# MRCS-odTester.net
KiCad netlist of a schematic drawn in EAGLE
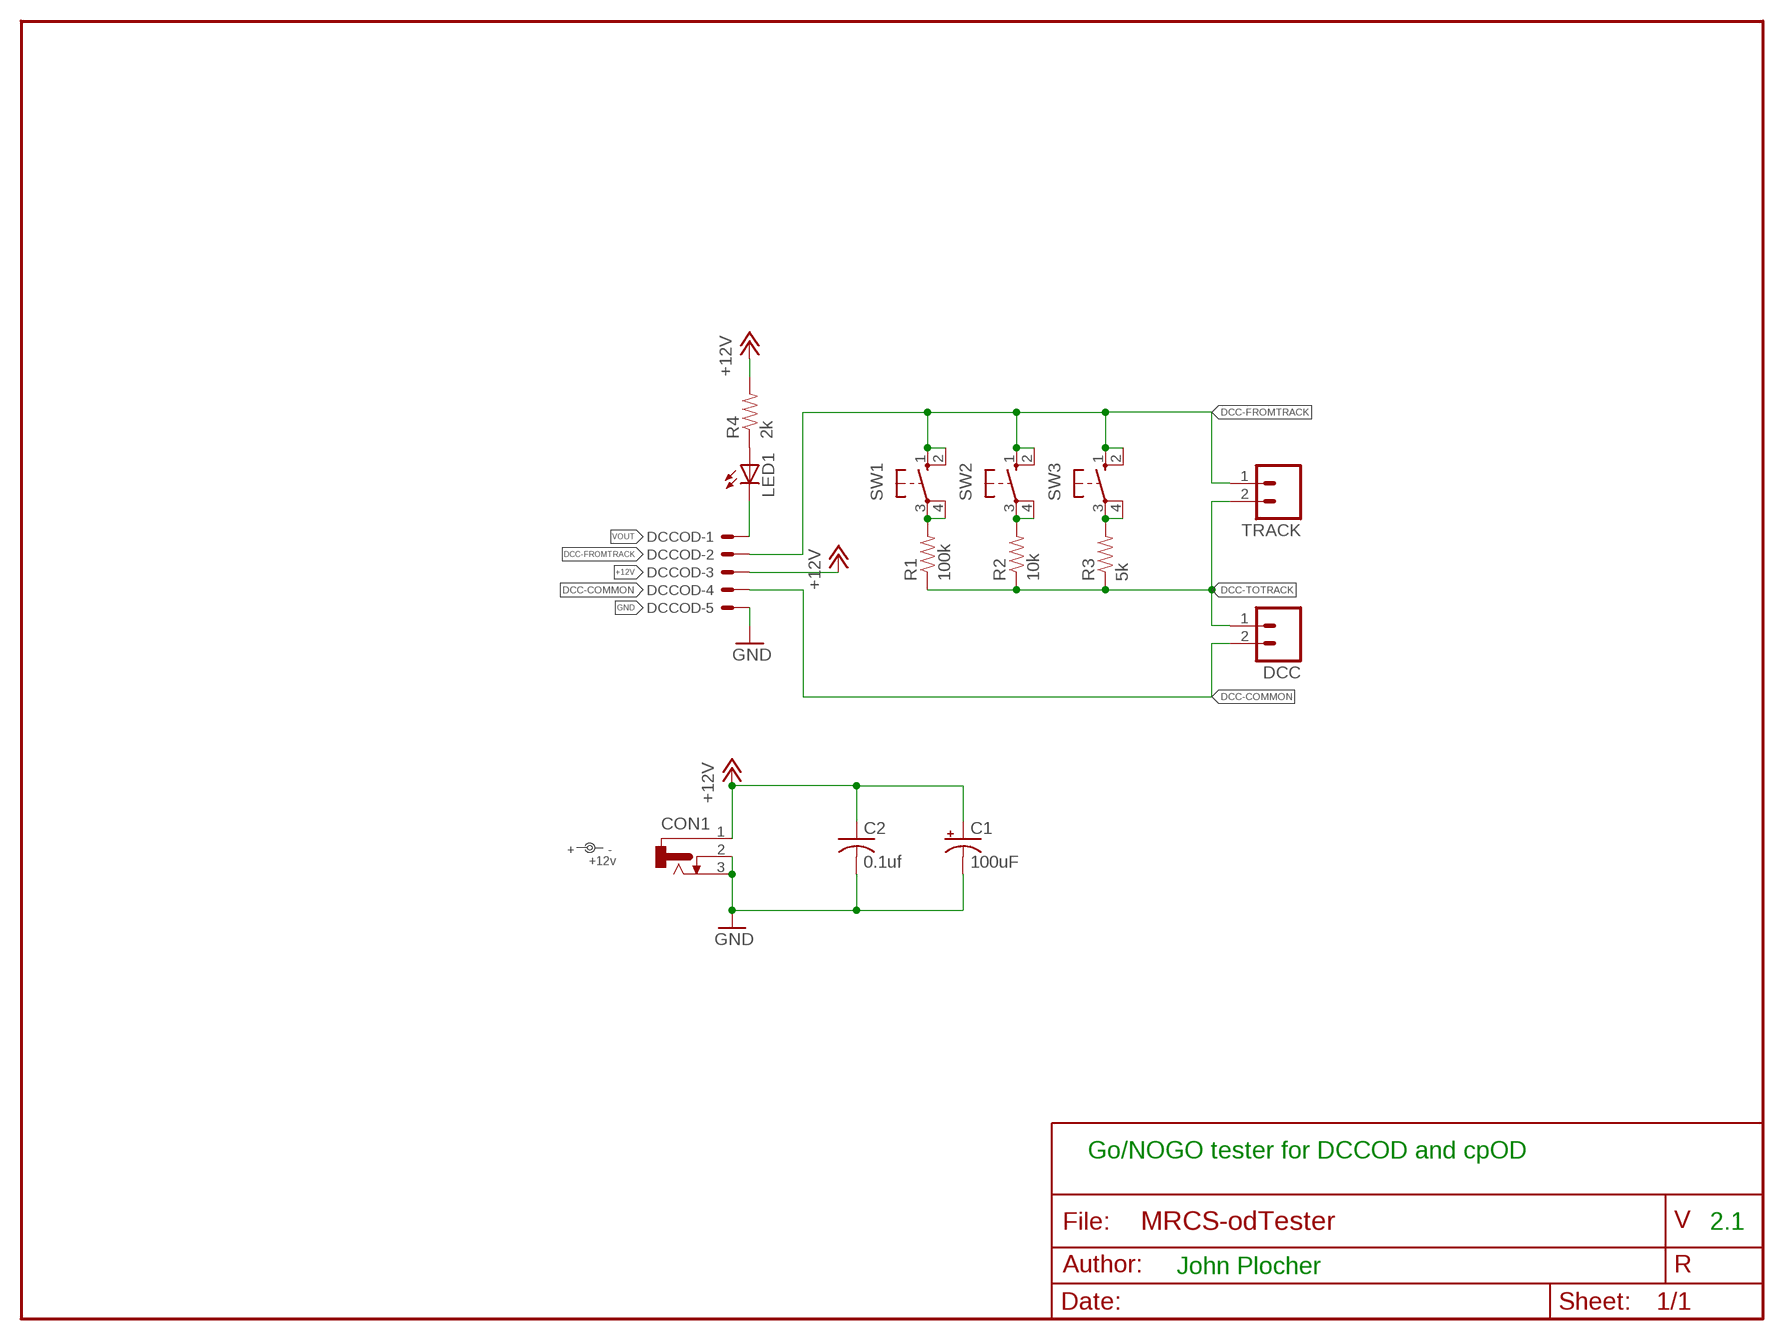
[diagram p0: schematic, sheet 1]

(export (version "E")
  (design (tool "Eeschema 10.0.6"))
  (components
    (comp (ref "C1")
      (value "100uF")
      (footprint "eagle-import:E3.5-10")
      (libsource (lib "eagle-import") (part "CAP-POLPTH-3.5MM"))
    )
    (comp (ref "C2")
      (value "0.1uf")
      (footprint "eagle-import:C050-024X044")
      (libsource (lib "eagle-import") (part "CAPPTH1"))
    )
    (comp (ref "CON1")
      (value "CONNECTOR-DC-POWER-RA")
      (footprint "eagle-import:DCJ0202")
      (libsource (lib "eagle-import") (part "CONNECTOR-DC-POWER-RA"))
    )
    (comp (ref "DCC")
      (value "CONNECTOR-M02508-LOCK")
      (footprint "eagle-import:MSTB2")
      (libsource (lib "eagle-import") (part "CONNECTOR-M02508-LOCK"))
    )
    (comp (ref "DCCOD")
      (value "KK-156-5")
      (footprint "eagle-import:KK-156-5")
      (libsource (lib "eagle-import") (part "KK-156-5"))
    )
    (comp (ref "LED1")
      (value "LEDLED5MM")
      (footprint "eagle-import:LED5MM")
      (libsource (lib "eagle-import") (part "LEDLED5MM"))
    )
    (comp (ref "R1")
      (value "100k")
      (footprint "eagle-import:AXIAL-0.4-RES")
      (libsource (lib "eagle-import") (part "RPTH04"))
    )
    (comp (ref "R2")
      (value "10k")
      (footprint "eagle-import:AXIAL-0.4-RES")
      (libsource (lib "eagle-import") (part "RPTH04"))
    )
    (comp (ref "R3")
      (value "5k")
      (footprint "eagle-import:AXIAL-0.4-RES")
      (libsource (lib "eagle-import") (part "RPTH04"))
    )
    (comp (ref "R4")
      (value "2k")
      (footprint "eagle-import:AXIAL-0.4-RES")
      (libsource (lib "eagle-import") (part "RPTH04"))
    )
    (comp (ref "SW1")
      (value "SWITCH-10-XX")
      (footprint "eagle-import:B3F-10XX")
      (libsource (lib "eagle-import") (part "SWITCH-10-XX"))
    )
    (comp (ref "SW2")
      (value "SWITCH-10-XX")
      (footprint "eagle-import:B3F-10XX")
      (libsource (lib "eagle-import") (part "SWITCH-10-XX"))
    )
    (comp (ref "SW3")
      (value "SWITCH-10-XX")
      (footprint "eagle-import:B3F-10XX")
      (libsource (lib "eagle-import") (part "SWITCH-10-XX"))
    )
    (comp (ref "TRACK")
      (value "CONNECTOR-M02508-LOCK")
      (footprint "eagle-import:MSTB2")
      (libsource (lib "eagle-import") (part "CONNECTOR-M02508-LOCK"))
    )
    (comp (ref "U$1")
      (value "+12v")
      (footprint "eagle-import:PWR_LABEL")
      (libsource (lib "eagle-import") (part "DOC-POWER_LABEL"))
    )
  )
  (nets
    (net (code "1") (name "+12V") (class "Default")
      (node (ref "C1") (pin "+") (pinfunction "+_+") (pintype "passive"))
      (node (ref "C2") (pin "1") (pinfunction "1_1") (pintype "passive"))
      (node (ref "CON1") (pin "1") (pinfunction "1_1") (pintype "passive"))
      (node (ref "DCCOD") (pin "3") (pinfunction "S_3") (pintype "passive"))
      (node (ref "R4") (pin "P$2") (pinfunction "2_P$2") (pintype "passive"))
    )
    (net (code "2") (name "DCC-COMMON") (class "Default")
      (node (ref "DCC") (pin "2") (pinfunction "B_2") (pintype "passive"))
      (node (ref "DCCOD") (pin "4") (pinfunction "S_4") (pintype "passive"))
    )
    (net (code "3") (name "DCC-FROMTRACK") (class "Default")
      (node (ref "DCCOD") (pin "2") (pinfunction "S_2") (pintype "passive"))
      (node (ref "SW1") (pin "1") (pinfunction "S_1") (pintype "passive"))
      (node (ref "SW1") (pin "2") (pinfunction "S1_2") (pintype "passive"))
      (node (ref "SW2") (pin "1") (pinfunction "S_1") (pintype "passive"))
      (node (ref "SW2") (pin "2") (pinfunction "S1_2") (pintype "passive"))
      (node (ref "SW3") (pin "1") (pinfunction "S_1") (pintype "passive"))
      (node (ref "SW3") (pin "2") (pinfunction "S1_2") (pintype "passive"))
      (node (ref "TRACK") (pin "1") (pinfunction "A_1") (pintype "passive"))
    )
    (net (code "4") (name "DCC-TOTRACK") (class "Default")
      (node (ref "DCC") (pin "1") (pinfunction "A_1") (pintype "passive"))
      (node (ref "R1") (pin "P$1") (pinfunction "1_P$1") (pintype "passive"))
      (node (ref "R2") (pin "P$1") (pinfunction "1_P$1") (pintype "passive"))
      (node (ref "R3") (pin "P$1") (pinfunction "1_P$1") (pintype "passive"))
      (node (ref "TRACK") (pin "2") (pinfunction "B_2") (pintype "passive"))
    )
    (net (code "5") (name "GND") (class "Default")
      (node (ref "C1") (pin "-") (pinfunction "-_-") (pintype "passive"))
      (node (ref "C2") (pin "2") (pinfunction "2_2") (pintype "passive"))
      (node (ref "CON1") (pin "2") (pinfunction "2_2") (pintype "passive"))
      (node (ref "CON1") (pin "3") (pinfunction "3_3") (pintype "passive"))
      (node (ref "DCCOD") (pin "5") (pinfunction "S_5") (pintype "passive"))
    )
    (net (code "6") (name "Net-(R1-2)") (class "Default")
      (node (ref "R1") (pin "P$2") (pinfunction "2_P$2") (pintype "passive"))
      (node (ref "SW1") (pin "3") (pinfunction "P_3") (pintype "passive"))
      (node (ref "SW1") (pin "4") (pinfunction "P1_4") (pintype "passive"))
    )
    (net (code "7") (name "Net-(R2-2)") (class "Default")
      (node (ref "R2") (pin "P$2") (pinfunction "2_P$2") (pintype "passive"))
      (node (ref "SW2") (pin "3") (pinfunction "P_3") (pintype "passive"))
      (node (ref "SW2") (pin "4") (pinfunction "P1_4") (pintype "passive"))
    )
    (net (code "8") (name "Net-(R3-2)") (class "Default")
      (node (ref "R3") (pin "P$2") (pinfunction "2_P$2") (pintype "passive"))
      (node (ref "SW3") (pin "3") (pinfunction "P_3") (pintype "passive"))
      (node (ref "SW3") (pin "4") (pinfunction "P1_4") (pintype "passive"))
    )
    (net (code "9") (name "Net-(R4-1)") (class "Default")
      (node (ref "LED1") (pin "A") (pinfunction "A_A") (pintype "passive"))
      (node (ref "R4") (pin "P$1") (pinfunction "1_P$1") (pintype "passive"))
    )
    (net (code "10") (name "VOUT") (class "Default")
      (node (ref "DCCOD") (pin "1") (pinfunction "S_1") (pintype "passive"))
      (node (ref "LED1") (pin "K") (pinfunction "C_K") (pintype "passive"))
    )
  )
)
